# board.net
KiCad netlist of a schematic drawn in EAGLE
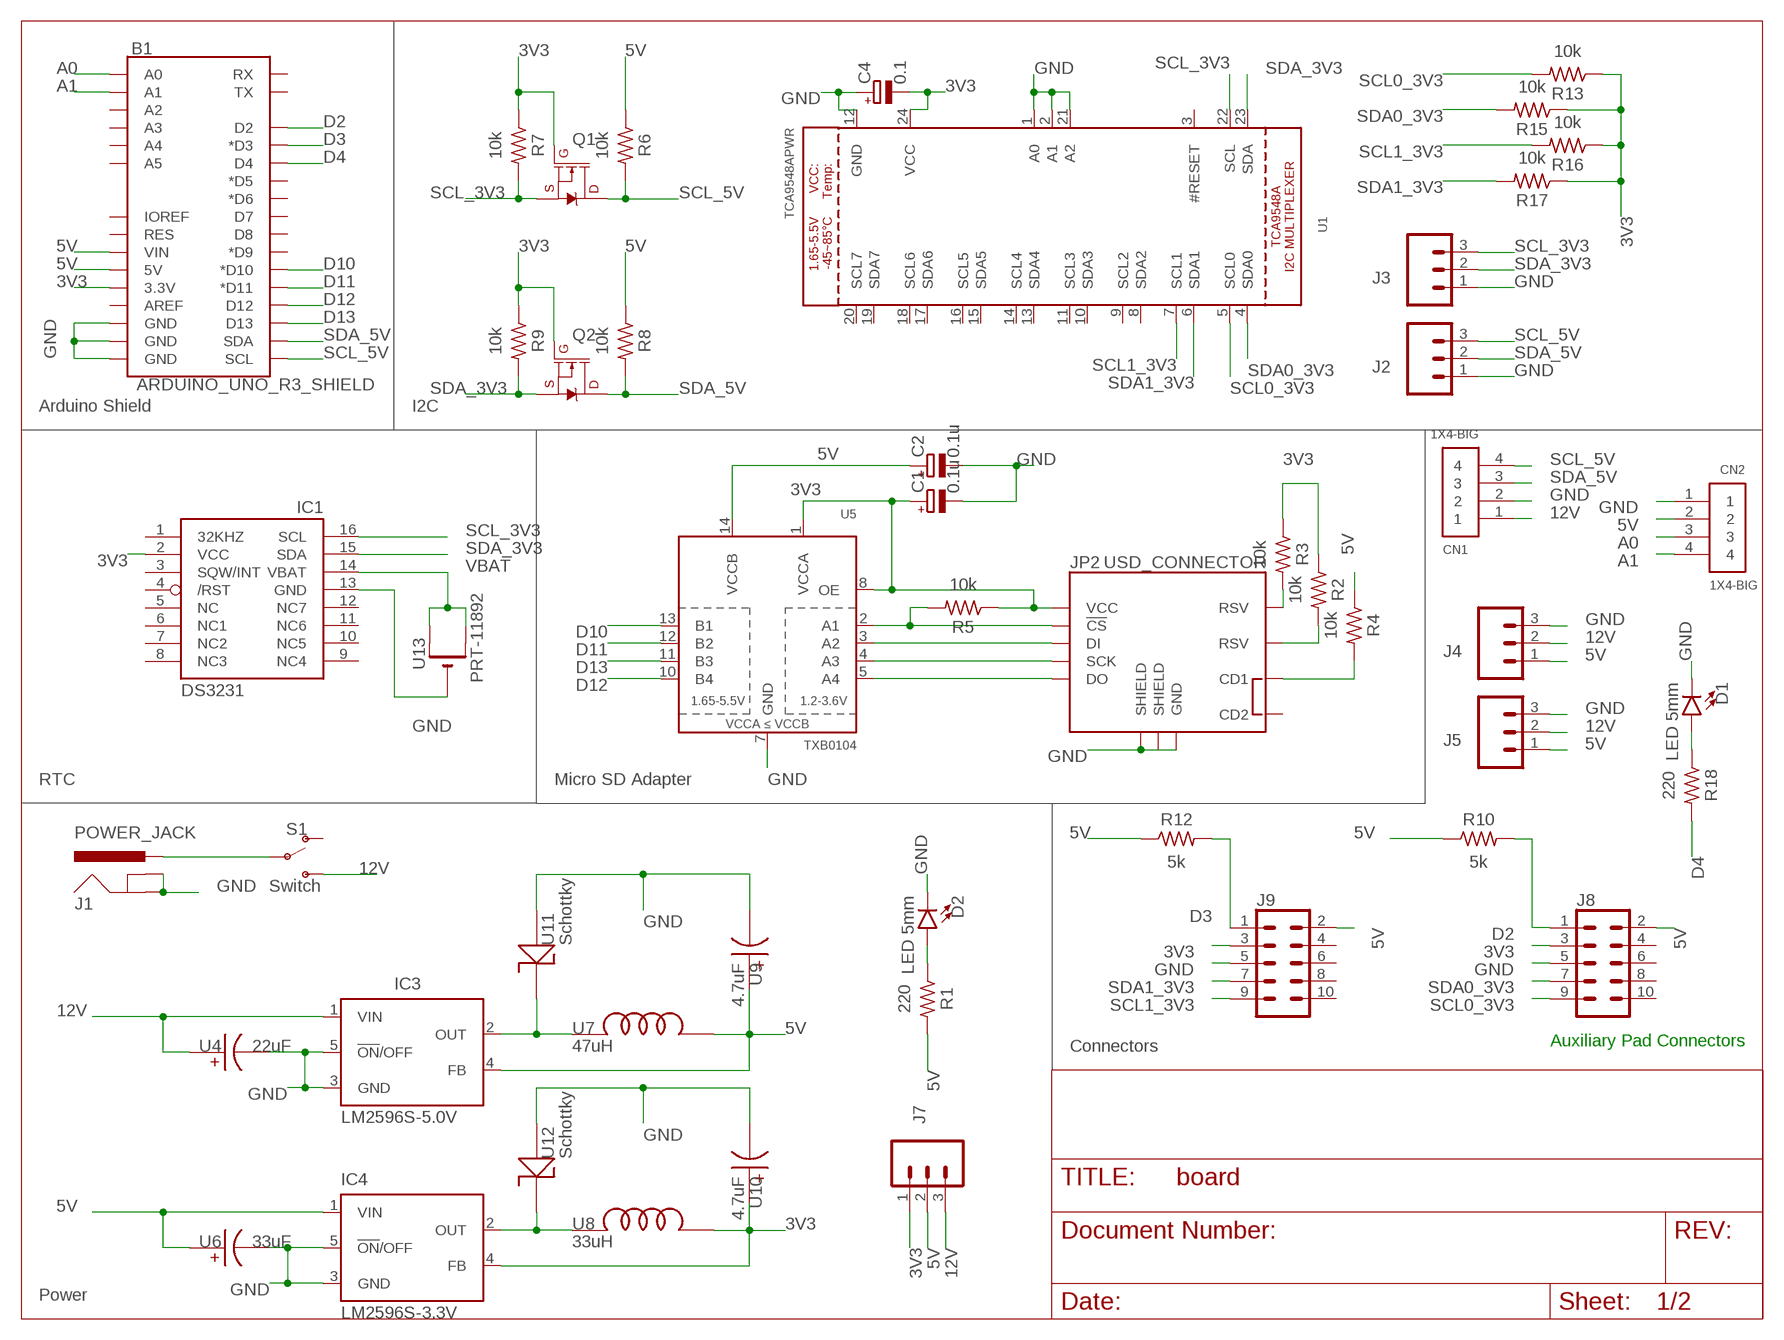
[diagram p0: schematic, sheet 1]
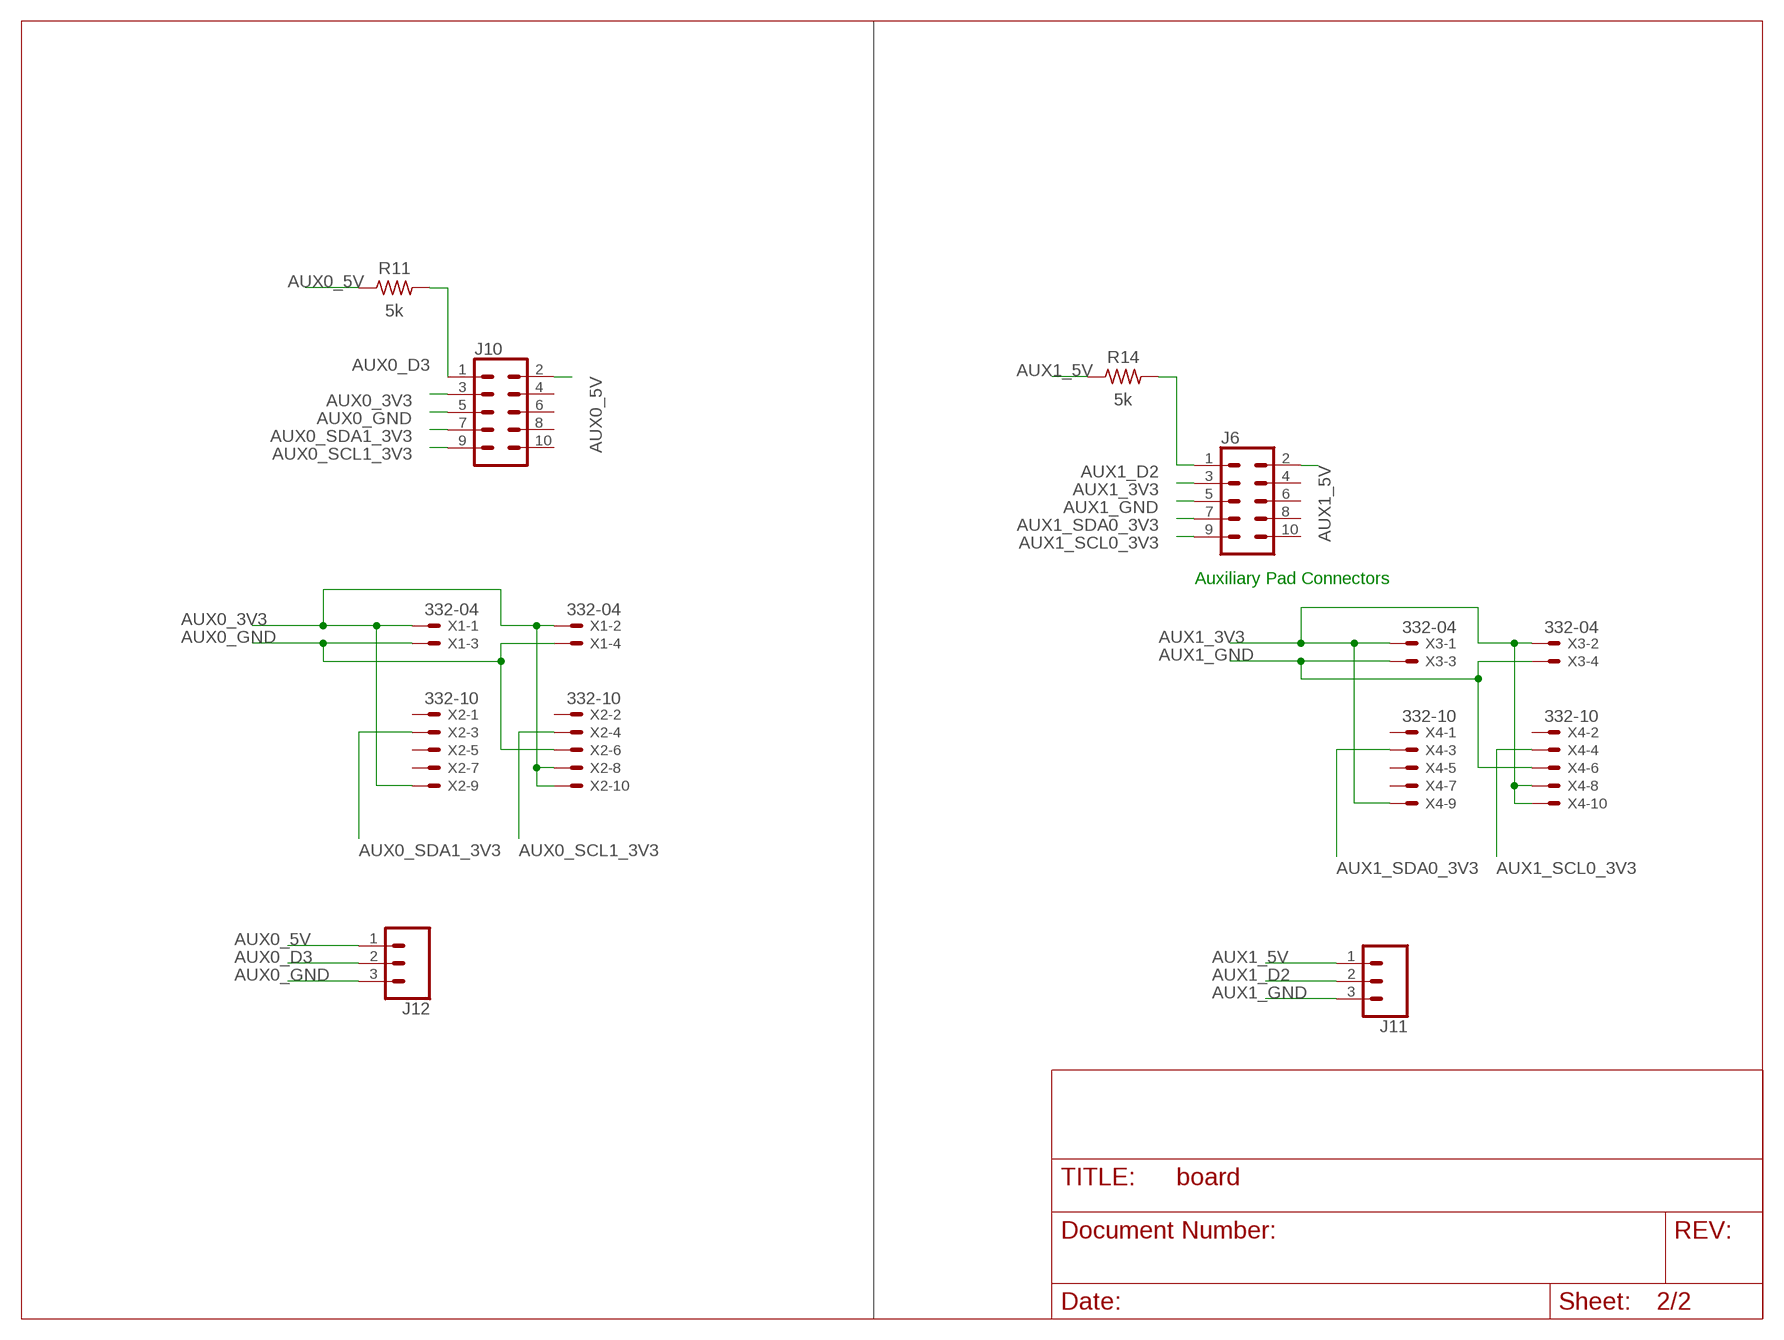
[diagram p1: schematic, sheet 2]

(export (version "E")
  (design (tool "Eeschema 10.0.6"))
  (components
    (comp (ref "B1")
      (value "ARDUINO_UNO_R3_SHIELD")
      (footprint "eagle-import:UNO_R3_SHIELD_NOLABELS_LOCK")
      (libsource (lib "eagle-import") (part "ARDUINO_UNO_R3_SHIELDUNO_R3_SHIELD_NOLABELS_LOCK"))
    )
    (comp (ref "C1")
      (value "0.1u")
      (footprint "eagle-import:CAPMP3216X180N")
      (libsource (lib "eagle-import") (part "C-POLTANTALUM-1206(3216-METRIC)_"))
    )
    (comp (ref "C2")
      (value "0.1u")
      (footprint "eagle-import:CAPMP3216X180N")
      (libsource (lib "eagle-import") (part "C-POLTANTALUM-1206(3216-METRIC)_"))
    )
    (comp (ref "C4")
      (value "0.1")
      (footprint "eagle-import:CAPMP3216X180N")
      (libsource (lib "eagle-import") (part "C-POLTANTALUM-1206(3216-METRIC)_"))
    )
    (comp (ref "CN1")
      (value "1X4-BIG")
      (footprint "eagle-import:1X04-BIG")
      (libsource (lib "eagle-import") (part "1X4-BIG"))
    )
    (comp (ref "CN2")
      (value "1X4-BIG")
      (footprint "eagle-import:1X04-BIG")
      (libsource (lib "eagle-import") (part "1X4-BIG"))
    )
    (comp (ref "D1")
      (value "LED 5mm")
      (footprint "eagle-import:LED_5MM")
      (fields (field (name "PARTNO") "FLC INVENTORY"))
      (libsource (lib "eagle-import") (part "LED5MM"))
    )
    (comp (ref "D2")
      (value "LED 5mm")
      (footprint "eagle-import:LED_5MM")
      (fields (field (name "PARTNO") "FLC INVENTORY"))
      (libsource (lib "eagle-import") (part "LED5MM"))
    )
    (comp (ref "IC1")
      (value "DS3231/SO")
      (footprint "eagle-import:SO16W")
      (libsource (lib "eagle-import") (part "DS3231/SO"))
    )
    (comp (ref "IC3")
      (value "LM2596S-5.0V")
      (footprint "eagle-import:TO263-5")
      (fields
        (field (name "MF") "NATIONAL SEMICONDUCTOR")
        (field (name "MPN") "LM2596S-ADJ/NOPB")
        (field (name "PARTNO") "FLC INVENTORY")
      )
      (libsource (lib "eagle-import") (part "LM2596S"))
    )
    (comp (ref "IC4")
      (value "LM2596S-3.3V")
      (footprint "eagle-import:TO263-5")
      (fields
        (field (name "MF") "NATIONAL SEMICONDUCTOR")
        (field (name "MPN") "LM2596S-ADJ/NOPB")
        (field (name "PARTNO") "FLC INVENTORY")
      )
      (libsource (lib "eagle-import") (part "LM2596S"))
    )
    (comp (ref "J1")
      (value "POWER_JACK")
      (footprint "eagle-import:POWER_JACK_PTH")
      (fields (field (name "PARTNO") "FLC INVENTORY"))
      (libsource (lib "eagle-import") (part "POWER_JACK"))
    )
    (comp (ref "J2")
      (value "3-Pin Screw Terminal 5mm")
      (footprint "eagle-import:SCREWTERMINAL-5MM-3")
      (fields (field (name "PARTNO") "2057-EB21A-03-C-ND"))
      (libsource (lib "eagle-import") (part "CONN_03-SCREW-5MM"))
    )
    (comp (ref "J3")
      (value "3-Pin Screw Terminal 5mm")
      (footprint "eagle-import:SCREWTERMINAL-5MM-3")
      (fields (field (name "PARTNO") "2057-EB21A-03-C-ND"))
      (libsource (lib "eagle-import") (part "CONN_03-SCREW-5MM"))
    )
    (comp (ref "J4")
      (value "3-Pin Screw Terminal 5mm")
      (footprint "eagle-import:SCREWTERMINAL-5MM-3")
      (fields (field (name "PARTNO") "2057-EB21A-03-C-ND"))
      (libsource (lib "eagle-import") (part "CONN_03-SCREW-5MM"))
    )
    (comp (ref "J5")
      (value "3-Pin Screw Terminal 5mm")
      (footprint "eagle-import:SCREWTERMINAL-5MM-3")
      (fields (field (name "PARTNO") "2057-EB21A-03-C-ND"))
      (libsource (lib "eagle-import") (part "CONN_03-SCREW-5MM"))
    )
    (comp (ref "J7")
      (value "3-Pin Screw Terminal 5mm")
      (footprint "eagle-import:SCREWTERMINAL-5MM-3")
      (fields (field (name "PARTNO") "2057-EB21A-03-C-ND"))
      (libsource (lib "eagle-import") (part "CONN_03-SCREW-5MM"))
    )
    (comp (ref "J8")
      (value "2x6 0.1\" Shrouded Female Header")
      (footprint "eagle-import:2X5-SHROUDED_LOCK")
      (fields (field (name "PARTNO") "PRT-08506 and PRT-10650"))
      (libsource (lib "eagle-import") (part "CONN_05X2SHD_LOCK"))
    )
    (comp (ref "J9")
      (value "2x6 0.1\" Shrouded Female Header")
      (footprint "eagle-import:2X5-SHROUDED_LOCK")
      (fields (field (name "PARTNO") "PRT-08506 and PRT-10650"))
      (libsource (lib "eagle-import") (part "CONN_05X2SHD_LOCK"))
    )
    (comp (ref "JP2")
      (value "USD_CONNECTOR")
      (footprint "eagle-import:MICRO-SD-SOCKET-PP")
      (libsource (lib "eagle-import") (part "USD_CONNECTOR"))
    )
    (comp (ref "Q1")
      (value "220mA/50V/3.5Ω")
      (footprint "eagle-import:SOT23-3")
      (libsource (lib "eagle-import") (part "MOSFET-NCH-BSS138"))
    )
    (comp (ref "Q2")
      (value "220mA/50V/3.5Ω")
      (footprint "eagle-import:SOT23-3")
      (libsource (lib "eagle-import") (part "MOSFET-NCH-BSS138"))
    )
    (comp (ref "R1")
      (value "220")
      (footprint "eagle-import:RESC1608X60")
      (libsource (lib "eagle-import") (part "R-USCHIP-0603(1608-METRIC)_"))
    )
    (comp (ref "R2")
      (value "10k")
      (footprint "eagle-import:RESC1608X60")
      (libsource (lib "eagle-import") (part "R-USCHIP-0603(1608-METRIC)_"))
    )
    (comp (ref "R3")
      (value "10k")
      (footprint "eagle-import:RESC1608X60")
      (libsource (lib "eagle-import") (part "R-USCHIP-0603(1608-METRIC)_"))
    )
    (comp (ref "R4")
      (value "10k")
      (footprint "eagle-import:RESC1608X60")
      (libsource (lib "eagle-import") (part "R-USCHIP-0603(1608-METRIC)_"))
    )
    (comp (ref "R5")
      (value "10k")
      (footprint "eagle-import:RESC1608X60")
      (libsource (lib "eagle-import") (part "R-USCHIP-0603(1608-METRIC)_"))
    )
    (comp (ref "R6")
      (value "10k")
      (footprint "eagle-import:RESC1608X60")
      (libsource (lib "eagle-import") (part "R-USCHIP-0603(1608-METRIC)_"))
    )
    (comp (ref "R7")
      (value "10k")
      (footprint "eagle-import:RESC1608X60")
      (libsource (lib "eagle-import") (part "R-USCHIP-0603(1608-METRIC)_"))
    )
    (comp (ref "R8")
      (value "10k")
      (footprint "eagle-import:RESC1608X60")
      (libsource (lib "eagle-import") (part "R-USCHIP-0603(1608-METRIC)_"))
    )
    (comp (ref "R9")
      (value "10k")
      (footprint "eagle-import:RESC1608X60")
      (libsource (lib "eagle-import") (part "R-USCHIP-0603(1608-METRIC)_"))
    )
    (comp (ref "R10")
      (value "5k")
      (footprint "eagle-import:RESC1608X60")
      (libsource (lib "eagle-import") (part "R-USCHIP-0603(1608-METRIC)_"))
    )
    (comp (ref "R12")
      (value "5k")
      (footprint "eagle-import:RESC1608X60")
      (libsource (lib "eagle-import") (part "R-USCHIP-0603(1608-METRIC)_"))
    )
    (comp (ref "R13")
      (value "10k")
      (footprint "eagle-import:RESC1608X60")
      (libsource (lib "eagle-import") (part "R-USCHIP-0603(1608-METRIC)_"))
    )
    (comp (ref "R15")
      (value "10k")
      (footprint "eagle-import:RESC1608X60")
      (libsource (lib "eagle-import") (part "R-USCHIP-0603(1608-METRIC)_"))
    )
    (comp (ref "R16")
      (value "10k")
      (footprint "eagle-import:RESC1608X60")
      (libsource (lib "eagle-import") (part "R-USCHIP-0603(1608-METRIC)_"))
    )
    (comp (ref "R17")
      (value "10k")
      (footprint "eagle-import:RESC1608X60")
      (libsource (lib "eagle-import") (part "R-USCHIP-0603(1608-METRIC)_"))
    )
    (comp (ref "R18")
      (value "220")
      (footprint "eagle-import:RESC1608X60")
      (libsource (lib "eagle-import") (part "R-USCHIP-0603(1608-METRIC)_"))
    )
    (comp (ref "S1")
      (value "Switch")
      (footprint "eagle-import:SWITCH_SPDT_PTH_11.6X4.0MM")
      (fields (field (name "PARTNO") "EG2355-ND"))
      (libsource (lib "eagle-import") (part "SWITCH-SPDT-PTH-11.6X4.0MM"))
    )
    (comp (ref "U1")
      (value "TCA9548APWR")
      (footprint "eagle-import:TSSOP24")
      (libsource (lib "eagle-import") (part "TCA9548A"))
    )
    (comp (ref "U4")
      (value "22uF")
      (footprint "eagle-import:CAP_ALUM_22UF_20%_63V_SMD")
      (fields (field (name "PARTNO") "FLC INVENTORY"))
      (libsource (lib "eagle-import") (part "CAP_ALUM_22UF_20%_63V_SMD"))
    )
    (comp (ref "U5")
      (value "TXB0104")
      (footprint "eagle-import:SO14")
      (libsource (lib "eagle-import") (part "TXB0104PWRSOIC14"))
    )
    (comp (ref "U6")
      (value "33uF")
      (footprint "eagle-import:CAP_ALUM_33UF_20%_63V_SMD")
      (fields (field (name "PARTNO") "FLC INVENTORY"))
      (libsource (lib "eagle-import") (part "CAP_ALUM_33UF_20%_63V_SMD"))
    )
    (comp (ref "U7")
      (value "47uH")
      (footprint "eagle-import:FIXED_IND_47UH_3.8A_60_MOHM_SMD")
      (fields (field (name "PARTNO") "FLC INVENTORY"))
      (libsource (lib "eagle-import") (part "FIXED_IND_47UH_3.8A_60_MOHM_SMD"))
    )
    (comp (ref "U8")
      (value "33uH")
      (footprint "eagle-import:FIXED_IND_47UH_3.8A_60_MOHM_SMD")
      (fields (field (name "PARTNO") "FLC INVENTORY"))
      (libsource (lib "eagle-import") (part "FIXED_IND_47UH_3.8A_60_MOHM_SMD"))
    )
    (comp (ref "U9")
      (value "4.7uF")
      (footprint "eagle-import:CAP_ALUM_4.7UF_20%_100V_SMD")
      (fields (field (name "PARTNO") "FLC INVENTORY"))
      (libsource (lib "eagle-import") (part "CAP_ALUM_4.7_UF_20%_100V_SMD"))
    )
    (comp (ref "U10")
      (value "4.7uF")
      (footprint "eagle-import:CAP_ALUM_4.7UF_20%_100V_SMD")
      (fields (field (name "PARTNO") "FLC INVENTORY"))
      (libsource (lib "eagle-import") (part "CAP_ALUM_4.7_UF_20%_100V_SMD"))
    )
    (comp (ref "U11")
      (value "Schottky")
      (footprint "eagle-import:DIODE_SCHOTTKY_40V_3A_SMC")
      (fields (field (name "PARTNO") "FLC INVENTORY"))
      (libsource (lib "eagle-import") (part "DIODE_SCHOTTKY_40V_3A_SMC"))
    )
    (comp (ref "U12")
      (value "Schottky")
      (footprint "eagle-import:DIODE_SCHOTTKY_40V_3A_SMC")
      (fields (field (name "PARTNO") "FLC INVENTORY"))
      (libsource (lib "eagle-import") (part "DIODE_SCHOTTKY_40V_3A_SMC"))
    )
    (comp (ref "U13")
      (value "PRT-11892")
      (footprint "eagle-import:CR2032-SMD")
      (libsource (lib "eagle-import") (part "CR2032SMT"))
    )
    (comp (ref "J6")
      (value "2x6 0.1\" Shrouded Female Header")
      (footprint "eagle-import:2X5-SHROUDED_LOCK")
      (fields (field (name "PARTNO") "PRT-08506 and PRT-10650"))
      (libsource (lib "eagle-import") (part "CONN_05X2SHD_LOCK"))
    )
    (comp (ref "J10")
      (value "2x6 0.1\" Shrouded Female Header")
      (footprint "eagle-import:2X5-SHROUDED_LOCK")
      (fields (field (name "PARTNO") "PRT-08506 and PRT-10650"))
      (libsource (lib "eagle-import") (part "CONN_05X2SHD_LOCK"))
    )
    (comp (ref "J11")
      (value "CONN_03")
      (footprint "eagle-import:1X03")
      (libsource (lib "eagle-import") (part "CONN_03"))
    )
    (comp (ref "J12")
      (value "CONN_03")
      (footprint "eagle-import:1X03")
      (libsource (lib "eagle-import") (part "CONN_03"))
    )
    (comp (ref "R11")
      (value "5k")
      (footprint "eagle-import:RESC1608X60")
      (libsource (lib "eagle-import") (part "R-USCHIP-0603(1608-METRIC)_"))
    )
    (comp (ref "R14")
      (value "5k")
      (footprint "eagle-import:RESC1608X60")
      (libsource (lib "eagle-import") (part "R-USCHIP-0603(1608-METRIC)_"))
    )
    (comp (ref "X1")
      (value "332-04")
      (footprint "eagle-import:332-04")
      (libsource (lib "eagle-import") (part "332-04"))
    )
    (comp (ref "X2")
      (value "332-10")
      (footprint "eagle-import:332-10")
      (libsource (lib "eagle-import") (part "332-10"))
    )
    (comp (ref "X3")
      (value "332-04")
      (footprint "eagle-import:332-04")
      (libsource (lib "eagle-import") (part "332-04"))
    )
    (comp (ref "X4")
      (value "332-10")
      (footprint "eagle-import:332-10")
      (libsource (lib "eagle-import") (part "332-10"))
    )
  )
  (nets
    (net (code "1") (name "3V3") (class "Default")
      (node (ref "B1") (pin "3.3V") (pinfunction "3.3V_3.3V") (pintype "bidirectional"))
      (node (ref "C1") (pin "1") (pinfunction "+_1") (pintype "passive"))
      (node (ref "C4") (pin "2") (pinfunction "-_2") (pintype "passive"))
      (node (ref "IC1") (pin "2") (pinfunction "VCC_2") (pintype "power_in"))
      (node (ref "IC4") (pin "4") (pinfunction "FB_4") (pintype "input"))
      (node (ref "J7") (pin "1") (pinfunction "1_1") (pintype "passive"))
      (node (ref "J8") (pin "3") (pinfunction "3_3") (pintype "passive"))
      (node (ref "J9") (pin "3") (pinfunction "3_3") (pintype "passive"))
      (node (ref "JP2") (pin "VCC") (pinfunction "VCC_VCC") (pintype "bidirectional"))
      (node (ref "Q1") (pin "1") (pinfunction "G_1") (pintype "bidirectional"))
      (node (ref "Q2") (pin "1") (pinfunction "G_1") (pintype "bidirectional"))
      (node (ref "R13") (pin "1") (pinfunction "1_1") (pintype "passive"))
      (node (ref "R15") (pin "1") (pinfunction "1_1") (pintype "passive"))
      (node (ref "R16") (pin "1") (pinfunction "1_1") (pintype "passive"))
      (node (ref "R17") (pin "1") (pinfunction "1_1") (pintype "passive"))
      (node (ref "R2") (pin "1") (pinfunction "1_1") (pintype "passive"))
      (node (ref "R3") (pin "1") (pinfunction "1_1") (pintype "passive"))
      (node (ref "R5") (pin "1") (pinfunction "1_1") (pintype "passive"))
      (node (ref "R7") (pin "1") (pinfunction "1_1") (pintype "passive"))
      (node (ref "R9") (pin "1") (pinfunction "1_1") (pintype "passive"))
      (node (ref "U1") (pin "24") (pinfunction "VCC_24") (pintype "bidirectional"))
      (node (ref "U10") (pin "P$2") (pinfunction "P$2_P$2") (pintype "bidirectional"))
      (node (ref "U5") (pin "1") (pinfunction "VCCA_1") (pintype "bidirectional"))
      (node (ref "U5") (pin "8") (pinfunction "OE_8") (pintype "bidirectional"))
      (node (ref "U8") (pin "P$2") (pinfunction "P$2_P$2") (pintype "bidirectional"))
    )
    (net (code "2") (name "5V") (class "Default")
      (node (ref "B1") (pin "5V") (pinfunction "5V_5V") (pintype "bidirectional"))
      (node (ref "B1") (pin "VIN") (pinfunction "VIN_VIN") (pintype "bidirectional"))
      (node (ref "C2") (pin "1") (pinfunction "+_1") (pintype "passive"))
      (node (ref "CN2") (pin "2") (pinfunction "2_2") (pintype "bidirectional"))
      (node (ref "IC3") (pin "4") (pinfunction "FB_4") (pintype "input"))
      (node (ref "IC4") (pin "1") (pinfunction "VIN_1") (pintype "input"))
      (node (ref "J4") (pin "1") (pinfunction "1_1") (pintype "passive"))
      (node (ref "J5") (pin "1") (pinfunction "1_1") (pintype "passive"))
      (node (ref "J7") (pin "2") (pinfunction "2_2") (pintype "passive"))
      (node (ref "J8") (pin "2") (pinfunction "2_2") (pintype "passive"))
      (node (ref "J9") (pin "2") (pinfunction "2_2") (pintype "passive"))
      (node (ref "R1") (pin "2") (pinfunction "2_2") (pintype "passive"))
      (node (ref "R10") (pin "1") (pinfunction "1_1") (pintype "passive"))
      (node (ref "R12") (pin "1") (pinfunction "1_1") (pintype "passive"))
      (node (ref "R4") (pin "1") (pinfunction "1_1") (pintype "passive"))
      (node (ref "R6") (pin "1") (pinfunction "1_1") (pintype "passive"))
      (node (ref "R8") (pin "1") (pinfunction "1_1") (pintype "passive"))
      (node (ref "U5") (pin "14") (pinfunction "VCCB_14") (pintype "bidirectional"))
      (node (ref "U6") (pin "P$2") (pinfunction "P$2_P$2") (pintype "bidirectional"))
      (node (ref "U7") (pin "P$2") (pinfunction "P$2_P$2") (pintype "bidirectional"))
      (node (ref "U9") (pin "P$2") (pinfunction "P$2_P$2") (pintype "bidirectional"))
    )
    (net (code "3") (name "12V") (class "Default")
      (node (ref "CN1") (pin "1") (pinfunction "1_1") (pintype "bidirectional"))
      (node (ref "IC3") (pin "1") (pinfunction "VIN_1") (pintype "input"))
      (node (ref "J4") (pin "2") (pinfunction "2_2") (pintype "passive"))
      (node (ref "J5") (pin "2") (pinfunction "2_2") (pintype "passive"))
      (node (ref "J7") (pin "3") (pinfunction "3_3") (pintype "passive"))
      (node (ref "S1") (pin "3") (pinfunction "S_3") (pintype "passive"))
      (node (ref "U4") (pin "P$2") (pinfunction "P$2_P$2") (pintype "bidirectional"))
    )
    (net (code "4") (name "A0") (class "Default")
      (node (ref "B1") (pin "A0") (pinfunction "A0_A0") (pintype "bidirectional"))
      (node (ref "CN2") (pin "3") (pinfunction "3_3") (pintype "bidirectional"))
    )
    (net (code "5") (name "A1") (class "Default")
      (node (ref "B1") (pin "A1") (pinfunction "A1_A1") (pintype "bidirectional"))
      (node (ref "CN2") (pin "4") (pinfunction "4_4") (pintype "bidirectional"))
    )
    (net (code "6") (name "AUX0_3V3") (class "Default")
      (node (ref "J10") (pin "3") (pinfunction "3_3") (pintype "passive"))
      (node (ref "X1") (pin "1") (pinfunction "S_1") (pintype "passive"))
      (node (ref "X1") (pin "2") (pinfunction "S_2") (pintype "passive"))
      (node (ref "X2") (pin "10") (pinfunction "S_10") (pintype "passive"))
      (node (ref "X2") (pin "8") (pinfunction "S_8") (pintype "passive"))
      (node (ref "X2") (pin "9") (pinfunction "S_9") (pintype "passive"))
    )
    (net (code "7") (name "AUX0_5V") (class "Default")
      (node (ref "J10") (pin "2") (pinfunction "2_2") (pintype "passive"))
      (node (ref "J12") (pin "1") (pinfunction "1_1") (pintype "passive"))
      (node (ref "R11") (pin "1") (pinfunction "1_1") (pintype "passive"))
    )
    (net (code "8") (name "AUX0_D3") (class "Default")
      (node (ref "J10") (pin "1") (pinfunction "1_1") (pintype "passive"))
      (node (ref "J12") (pin "2") (pinfunction "2_2") (pintype "passive"))
      (node (ref "R11") (pin "2") (pinfunction "2_2") (pintype "passive"))
    )
    (net (code "9") (name "AUX0_GND") (class "Default")
      (node (ref "J10") (pin "5") (pinfunction "5_5") (pintype "passive"))
      (node (ref "J12") (pin "3") (pinfunction "3_3") (pintype "passive"))
      (node (ref "X1") (pin "3") (pinfunction "S_3") (pintype "passive"))
      (node (ref "X1") (pin "4") (pinfunction "S_4") (pintype "passive"))
      (node (ref "X2") (pin "6") (pinfunction "S_6") (pintype "passive"))
    )
    (net (code "10") (name "AUX0_SCL1_3V3") (class "Default")
      (node (ref "J10") (pin "9") (pinfunction "9_9") (pintype "passive"))
      (node (ref "X2") (pin "4") (pinfunction "S_4") (pintype "passive"))
    )
    (net (code "11") (name "AUX0_SDA1_3V3") (class "Default")
      (node (ref "J10") (pin "7") (pinfunction "7_7") (pintype "passive"))
      (node (ref "X2") (pin "3") (pinfunction "S_3") (pintype "passive"))
    )
    (net (code "12") (name "AUX1_3V3") (class "Default")
      (node (ref "J6") (pin "3") (pinfunction "3_3") (pintype "passive"))
      (node (ref "X3") (pin "1") (pinfunction "S_1") (pintype "passive"))
      (node (ref "X3") (pin "2") (pinfunction "S_2") (pintype "passive"))
      (node (ref "X4") (pin "10") (pinfunction "S_10") (pintype "passive"))
      (node (ref "X4") (pin "8") (pinfunction "S_8") (pintype "passive"))
      (node (ref "X4") (pin "9") (pinfunction "S_9") (pintype "passive"))
    )
    (net (code "13") (name "AUX1_5V") (class "Default")
      (node (ref "J11") (pin "1") (pinfunction "1_1") (pintype "passive"))
      (node (ref "J6") (pin "2") (pinfunction "2_2") (pintype "passive"))
      (node (ref "R14") (pin "1") (pinfunction "1_1") (pintype "passive"))
    )
    (net (code "14") (name "AUX1_D2") (class "Default")
      (node (ref "J11") (pin "2") (pinfunction "2_2") (pintype "passive"))
      (node (ref "J6") (pin "1") (pinfunction "1_1") (pintype "passive"))
      (node (ref "R14") (pin "2") (pinfunction "2_2") (pintype "passive"))
    )
    (net (code "15") (name "AUX1_GND") (class "Default")
      (node (ref "J11") (pin "3") (pinfunction "3_3") (pintype "passive"))
      (node (ref "J6") (pin "5") (pinfunction "5_5") (pintype "passive"))
      (node (ref "X3") (pin "3") (pinfunction "S_3") (pintype "passive"))
      (node (ref "X3") (pin "4") (pinfunction "S_4") (pintype "passive"))
      (node (ref "X4") (pin "6") (pinfunction "S_6") (pintype "passive"))
    )
    (net (code "16") (name "AUX1_SCL0_3V3") (class "Default")
      (node (ref "J6") (pin "9") (pinfunction "9_9") (pintype "passive"))
      (node (ref "X4") (pin "4") (pinfunction "S_4") (pintype "passive"))
    )
    (net (code "17") (name "AUX1_SDA0_3V3") (class "Default")
      (node (ref "J6") (pin "7") (pinfunction "7_7") (pintype "passive"))
      (node (ref "X4") (pin "3") (pinfunction "S_3") (pintype "passive"))
    )
    (net (code "18") (name "D2") (class "Default")
      (node (ref "B1") (pin "D2") (pinfunction "D2_D2") (pintype "bidirectional"))
      (node (ref "J8") (pin "1") (pinfunction "1_1") (pintype "passive"))
      (node (ref "R10") (pin "2") (pinfunction "2_2") (pintype "passive"))
    )
    (net (code "19") (name "D3") (class "Default")
      (node (ref "B1") (pin "D3") (pinfunction "*D3_D3") (pintype "bidirectional"))
      (node (ref "J9") (pin "1") (pinfunction "1_1") (pintype "passive"))
      (node (ref "R12") (pin "2") (pinfunction "2_2") (pintype "passive"))
    )
    (net (code "20") (name "D4") (class "Default")
      (node (ref "B1") (pin "D4") (pinfunction "D4_D4") (pintype "bidirectional"))
      (node (ref "R18") (pin "2") (pinfunction "2_2") (pintype "passive"))
    )
    (net (code "21") (name "D10") (class "Default")
      (node (ref "B1") (pin "D10") (pinfunction "*D10_D10") (pintype "bidirectional"))
      (node (ref "U5") (pin "13") (pinfunction "B1_13") (pintype "bidirectional"))
    )
    (net (code "22") (name "D11") (class "Default")
      (node (ref "B1") (pin "D11") (pinfunction "*D11_D11") (pintype "bidirectional"))
      (node (ref "U5") (pin "12") (pinfunction "B2_12") (pintype "bidirectional"))
    )
    (net (code "23") (name "D12") (class "Default")
      (node (ref "B1") (pin "D12") (pinfunction "D12_D12") (pintype "bidirectional"))
      (node (ref "U5") (pin "10") (pinfunction "B4_10") (pintype "bidirectional"))
    )
    (net (code "24") (name "D13") (class "Default")
      (node (ref "B1") (pin "D13") (pinfunction "D13_D13") (pintype "bidirectional"))
      (node (ref "U5") (pin "11") (pinfunction "B3_11") (pintype "bidirectional"))
    )
    (net (code "25") (name "GND") (class "Default")
      (node (ref "B1") (pin "GND@0") (pinfunction "GND_GND@0") (pintype "bidirectional"))
      (node (ref "B1") (pin "GND@1") (pinfunction "GND_GND@1") (pintype "bidirectional"))
      (node (ref "B1") (pin "GND@2") (pinfunction "GND_GND@2") (pintype "bidirectional"))
      (node (ref "C1") (pin "2") (pinfunction "-_2") (pintype "passive"))
      (node (ref "C2") (pin "2") (pinfunction "-_2") (pintype "passive"))
      (node (ref "C4") (pin "1") (pinfunction "+_1") (pintype "passive"))
      (node (ref "CN1") (pin "2") (pinfunction "2_2") (pintype "bidirectional"))
      (node (ref "CN2") (pin "1") (pinfunction "1_1") (pintype "bidirectional"))
      (node (ref "D1") (pin "K") (pinfunction "C_K") (pintype "passive"))
      (node (ref "D2") (pin "K") (pinfunction "C_K") (pintype "passive"))
      (node (ref "IC1") (pin "13") (pinfunction "GND_13") (pintype "power_in"))
      (node (ref "IC3") (pin "3") (pinfunction "GND_3") (pintype "power_in"))
      (node (ref "IC3") (pin "5") (pinfunction "~{ON}/OFF_5") (pintype "input"))
      (node (ref "IC4") (pin "3") (pinfunction "GND_3") (pintype "power_in"))
      (node (ref "IC4") (pin "5") (pinfunction "~{ON}/OFF_5") (pintype "input"))
      (node (ref "J1") (pin "GND") (pinfunction "GND_GND") (pintype "bidirectional"))
      (node (ref "J1") (pin "GNDBREAK") (pinfunction "GNDBREAK_GNDBREAK") (pintype "bidirectional"))
      (node (ref "J2") (pin "1") (pinfunction "1_1") (pintype "passive"))
      (node (ref "J3") (pin "1") (pinfunction "1_1") (pintype "passive"))
      (node (ref "J4") (pin "3") (pinfunction "3_3") (pintype "passive"))
      (node (ref "J5") (pin "3") (pinfunction "3_3") (pintype "passive"))
      (node (ref "J8") (pin "5") (pinfunction "5_5") (pintype "passive"))
      (node (ref "J9") (pin "5") (pinfunction "5_5") (pintype "passive"))
      (node (ref "JP2") (pin "GND") (pinfunction "GND_GND") (pintype "bidirectional"))
      (node (ref "JP2") (pin "GND1") (pinfunction "SHIELD_GND1") (pintype "bidirectional"))
      (node (ref "JP2") (pin "GND3") (pinfunction "SHIELD_GND3") (pintype "bidirectional"))
      (node (ref "U1") (pin "1") (pinfunction "A0_1") (pintype "bidirectional"))
      (node (ref "U1") (pin "12") (pinfunction "GND_12") (pintype "bidirectional"))
      (node (ref "U1") (pin "2") (pinfunction "A1_2") (pintype "bidirectional"))
      (node (ref "U1") (pin "21") (pinfunction "A2_21") (pintype "bidirectional"))
      (node (ref "U10") (pin "P$1") (pinfunction "P$1_P$1") (pintype "bidirectional"))
      (node (ref "U11") (pin "P$1") (pinfunction "P$1_P$1") (pintype "bidirectional"))
      (node (ref "U12") (pin "P$1") (pinfunction "P$1_P$1") (pintype "bidirectional"))
      (node (ref "U13") (pin "-") (pinfunction "-_-") (pintype "passive"))
      (node (ref "U4") (pin "P$1") (pinfunction "P$1_P$1") (pintype "bidirectional"))
      (node (ref "U5") (pin "7") (pinfunction "GND_7") (pintype "bidirectional"))
      (node (ref "U6") (pin "P$1") (pinfunction "P$1_P$1") (pintype "bidirectional"))
      (node (ref "U9") (pin "P$1") (pinfunction "P$1_P$1") (pintype "bidirectional"))
    )
    (net (code "26") (name "Net-(D1-PadA)") (class "Default")
      (node (ref "D1") (pin "A") (pinfunction "A_A") (pintype "passive"))
      (node (ref "R18") (pin "1") (pinfunction "1_1") (pintype "passive"))
    )
    (net (code "27") (name "Net-(D2-PadA)") (class "Default")
      (node (ref "D2") (pin "A") (pinfunction "A_A") (pintype "passive"))
      (node (ref "R1") (pin "1") (pinfunction "1_1") (pintype "passive"))
    )
    (net (code "28") (name "Net-(IC3-OUT)") (class "Default")
      (node (ref "IC3") (pin "2") (pinfunction "OUT_2") (pintype "output"))
      (node (ref "U11") (pin "P$2") (pinfunction "P$2_P$2") (pintype "bidirectional"))
      (node (ref "U7") (pin "P$1") (pinfunction "P$1_P$1") (pintype "bidirectional"))
    )
    (net (code "29") (name "Net-(IC4-OUT)") (class "Default")
      (node (ref "IC4") (pin "2") (pinfunction "OUT_2") (pintype "output"))
      (node (ref "U12") (pin "P$2") (pinfunction "P$2_P$2") (pintype "bidirectional"))
      (node (ref "U8") (pin "P$1") (pinfunction "P$1_P$1") (pintype "bidirectional"))
    )
    (net (code "30") (name "Net-(JP2-PadCD1)") (class "Default")
      (node (ref "JP2") (pin "CD1") (pinfunction "CD1_CD1") (pintype "bidirectional"))
      (node (ref "R4") (pin "2") (pinfunction "2_2") (pintype "passive"))
    )
    (net (code "31") (name "Net-(JP2-RSV-PadRSV1)") (class "Default")
      (node (ref "JP2") (pin "RSV1") (pinfunction "RSV_RSV1") (pintype "bidirectional"))
      (node (ref "R3") (pin "2") (pinfunction "2_2") (pintype "passive"))
    )
    (net (code "32") (name "Net-(JP2-RSV-PadRSV2)") (class "Default")
      (node (ref "JP2") (pin "RSV2") (pinfunction "RSV_RSV2") (pintype "bidirectional"))
      (node (ref "R2") (pin "2") (pinfunction "2_2") (pintype "passive"))
    )
    (net (code "33") (name "Net-(JP2-SCK)") (class "Default")
      (node (ref "JP2") (pin "SCLK") (pinfunction "SCK_SCLK") (pintype "bidirectional"))
      (node (ref "U5") (pin "4") (pinfunction "A3_4") (pintype "bidirectional"))
    )
    (net (code "34") (name "Net-(JP2-~{CS})") (class "Default")
      (node (ref "JP2") (pin "CS") (pinfunction "~{CS}_CS") (pintype "bidirectional"))
      (node (ref "R5") (pin "2") (pinfunction "2_2") (pintype "passive"))
      (node (ref "U5") (pin "2") (pinfunction "A1_2") (pintype "bidirectional"))
    )
    (net (code "35") (name "Net-(S1-P)") (class "Default")
      (node (ref "J1") (pin "PWR") (pinfunction "PWR_PWR") (pintype "bidirectional"))
      (node (ref "S1") (pin "2") (pinfunction "P_2") (pintype "passive"))
    )
    (net (code "36") (name "Net-(U5-A2)") (class "Default")
      (node (ref "JP2") (pin "DI") (pinfunction "DI_DI") (pintype "bidirectional"))
      (node (ref "U5") (pin "3") (pinfunction "A2_3") (pintype "bidirectional"))
    )
    (net (code "37") (name "Net-(U5-A4)") (class "Default")
      (node (ref "JP2") (pin "DO") (pinfunction "DO_DO") (pintype "bidirectional"))
      (node (ref "U5") (pin "5") (pinfunction "A4_5") (pintype "bidirectional"))
    )
    (net (code "38") (name "SCL0_3V3") (class "Default")
      (node (ref "J8") (pin "9") (pinfunction "9_9") (pintype "passive"))
      (node (ref "R13") (pin "2") (pinfunction "2_2") (pintype "passive"))
      (node (ref "U1") (pin "5") (pinfunction "SCL0_5") (pintype "bidirectional"))
    )
    (net (code "39") (name "SCL1_3V3") (class "Default")
      (node (ref "J9") (pin "9") (pinfunction "9_9") (pintype "passive"))
      (node (ref "R16") (pin "2") (pinfunction "2_2") (pintype "passive"))
      (node (ref "U1") (pin "7") (pinfunction "SCL1_7") (pintype "bidirectional"))
    )
    (net (code "40") (name "SCL_3V3") (class "Default")
      (node (ref "IC1") (pin "16") (pinfunction "SCL_16") (pintype "bidirectional"))
      (node (ref "J3") (pin "3") (pinfunction "3_3") (pintype "passive"))
      (node (ref "Q1") (pin "2") (pinfunction "S_2") (pintype "bidirectional"))
      (node (ref "R7") (pin "2") (pinfunction "2_2") (pintype "passive"))
      (node (ref "U1") (pin "22") (pinfunction "SCL_22") (pintype "bidirectional"))
    )
    (net (code "41") (name "SCL_5V") (class "Default")
      (node (ref "B1") (pin "SCL") (pinfunction "SCL_SCL") (pintype "bidirectional"))
      (node (ref "CN1") (pin "4") (pinfunction "4_4") (pintype "bidirectional"))
      (node (ref "J2") (pin "3") (pinfunction "3_3") (pintype "passive"))
      (node (ref "Q1") (pin "3") (pinfunction "D_3") (pintype "bidirectional"))
      (node (ref "R6") (pin "2") (pinfunction "2_2") (pintype "passive"))
    )
    (net (code "42") (name "SDA0_3V3") (class "Default")
      (node (ref "J8") (pin "7") (pinfunction "7_7") (pintype "passive"))
      (node (ref "R15") (pin "2") (pinfunction "2_2") (pintype "passive"))
      (node (ref "U1") (pin "4") (pinfunction "SDA0_4") (pintype "bidirectional"))
    )
    (net (code "43") (name "SDA1_3V3") (class "Default")
      (node (ref "J9") (pin "7") (pinfunction "7_7") (pintype "passive"))
      (node (ref "R17") (pin "2") (pinfunction "2_2") (pintype "passive"))
      (node (ref "U1") (pin "6") (pinfunction "SDA1_6") (pintype "bidirectional"))
    )
    (net (code "44") (name "SDA_3V3") (class "Default")
      (node (ref "IC1") (pin "15") (pinfunction "SDA_15") (pintype "bidirectional"))
      (node (ref "J3") (pin "2") (pinfunction "2_2") (pintype "passive"))
      (node (ref "Q2") (pin "2") (pinfunction "S_2") (pintype "bidirectional"))
      (node (ref "R9") (pin "2") (pinfunction "2_2") (pintype "passive"))
      (node (ref "U1") (pin "23") (pinfunction "SDA_23") (pintype "bidirectional"))
    )
    (net (code "45") (name "SDA_5V") (class "Default")
      (node (ref "B1") (pin "SDA") (pinfunction "SDA_SDA") (pintype "bidirectional"))
      (node (ref "CN1") (pin "3") (pinfunction "3_3") (pintype "bidirectional"))
      (node (ref "J2") (pin "2") (pinfunction "2_2") (pintype "passive"))
      (node (ref "Q2") (pin "3") (pinfunction "D_3") (pintype "bidirectional"))
      (node (ref "R8") (pin "2") (pinfunction "2_2") (pintype "passive"))
    )
    (net (code "46") (name "VBAT") (class "Default")
      (node (ref "IC1") (pin "14") (pinfunction "VBAT_14") (pintype "power_in"))
      (node (ref "U13") (pin "+$1") (pinfunction "+_+$1") (pintype "passive"))
      (node (ref "U13") (pin "+$2") (pinfunction "+1_+$2") (pintype "passive"))
    )
    (net (code "47") (name "unconnected-(B1-*D5-PadD5)") (class "Default")
      (node (ref "B1") (pin "D5") (pinfunction "*D5_D5") (pintype "bidirectional"))
    )
    (net (code "48") (name "unconnected-(B1-*D6-PadD6)") (class "Default")
      (node (ref "B1") (pin "D6") (pinfunction "*D6_D6") (pintype "bidirectional"))
    )
    (net (code "49") (name "unconnected-(B1-*D9-PadD9)") (class "Default")
      (node (ref "B1") (pin "D9") (pinfunction "*D9_D9") (pintype "bidirectional"))
    )
    (net (code "50") (name "unconnected-(B1-PadA2)") (class "Default")
      (node (ref "B1") (pin "A2") (pinfunction "A2_A2") (pintype "bidirectional"))
    )
    (net (code "51") (name "unconnected-(B1-PadA3)") (class "Default")
      (node (ref "B1") (pin "A3") (pinfunction "A3_A3") (pintype "bidirectional"))
    )
    (net (code "52") (name "unconnected-(B1-PadA4)") (class "Default")
      (node (ref "B1") (pin "A4") (pinfunction "A4_A4") (pintype "bidirectional"))
    )
    (net (code "53") (name "unconnected-(B1-PadA5)") (class "Default")
      (node (ref "B1") (pin "A5") (pinfunction "A5_A5") (pintype "bidirectional"))
    )
    (net (code "54") (name "unconnected-(B1-PadAREF)") (class "Default")
      (node (ref "B1") (pin "AREF") (pinfunction "AREF_AREF") (pintype "bidirectional"))
    )
    (net (code "55") (name "unconnected-(B1-PadD7)") (class "Default")
      (node (ref "B1") (pin "D7") (pinfunction "D7_D7") (pintype "bidirectional"))
    )
    (net (code "56") (name "unconnected-(B1-PadD8)") (class "Default")
      (node (ref "B1") (pin "D8") (pinfunction "D8_D8") (pintype "bidirectional"))
    )
    (net (code "57") (name "unconnected-(B1-PadIOREF)") (class "Default")
      (node (ref "B1") (pin "IOREF") (pinfunction "IOREF_IOREF") (pintype "bidirectional"))
    )
    (net (code "58") (name "unconnected-(B1-PadRES)") (class "Default")
      (node (ref "B1") (pin "RES") (pinfunction "RES_RES") (pintype "bidirectional"))
    )
    (net (code "59") (name "unconnected-(B1-PadRX)") (class "Default")
      (node (ref "B1") (pin "RX") (pinfunction "RX_RX") (pintype "bidirectional"))
    )
    (net (code "60") (name "unconnected-(B1-PadTX)") (class "Default")
      (node (ref "B1") (pin "TX") (pinfunction "TX_TX") (pintype "bidirectional"))
    )
    (net (code "61") (name "unconnected-(IC1-32KHZ-Pad1)") (class "Default")
      (node (ref "IC1") (pin "1") (pinfunction "32KHZ_1") (pintype "output"))
    )
    (net (code "62") (name "unconnected-(IC1-NC-Pad5)") (class "Default")
      (node (ref "IC1") (pin "5") (pinfunction "NC_5") (pintype "no_connect"))
    )
    (net (code "63") (name "unconnected-(IC1-NC1-Pad6)") (class "Default")
      (node (ref "IC1") (pin "6") (pinfunction "NC1_6") (pintype "no_connect"))
    )
    (net (code "64") (name "unconnected-(IC1-NC2-Pad7)") (class "Default")
      (node (ref "IC1") (pin "7") (pinfunction "NC2_7") (pintype "no_connect"))
    )
    (net (code "65") (name "unconnected-(IC1-NC3-Pad8)") (class "Default")
      (node (ref "IC1") (pin "8") (pinfunction "NC3_8") (pintype "no_connect"))
    )
    (net (code "66") (name "unconnected-(IC1-NC4-Pad9)") (class "Default")
      (node (ref "IC1") (pin "9") (pinfunction "NC4_9") (pintype "no_connect"))
    )
    (net (code "67") (name "unconnected-(IC1-NC5-Pad10)") (class "Default")
      (node (ref "IC1") (pin "10") (pinfunction "NC5_10") (pintype "no_connect"))
    )
    (net (code "68") (name "unconnected-(IC1-NC6-Pad11)") (class "Default")
      (node (ref "IC1") (pin "11") (pinfunction "NC6_11") (pintype "no_connect"))
    )
    (net (code "69") (name "unconnected-(IC1-NC7-Pad12)") (class "Default")
      (node (ref "IC1") (pin "12") (pinfunction "NC7_12") (pintype "no_connect"))
    )
    (net (code "70") (name "unconnected-(IC1-SQW{slash}INT-Pad3)") (class "Default")
      (node (ref "IC1") (pin "3") (pinfunction "SQW/INT_3") (pintype "output"))
    )
    (net (code "71") (name "unconnected-(IC1-{slash}RST-Pad4)") (class "Default")
      (node (ref "IC1") (pin "4") (pinfunction "/RST_4") (pintype "passive"))
    )
    (net (code "72") (name "unconnected-(J6-Pad4)") (class "Default")
      (node (ref "J6") (pin "4") (pinfunction "4_4") (pintype "passive"))
    )
    (net (code "73") (name "unconnected-(J6-Pad6)") (class "Default")
      (node (ref "J6") (pin "6") (pinfunction "6_6") (pintype "passive"))
    )
    (net (code "74") (name "unconnected-(J6-Pad8)") (class "Default")
      (node (ref "J6") (pin "8") (pinfunction "8_8") (pintype "passive"))
    )
    (net (code "75") (name "unconnected-(J6-Pad10)") (class "Default")
      (node (ref "J6") (pin "10") (pinfunction "10_10") (pintype "passive"))
    )
    (net (code "76") (name "unconnected-(J8-Pad4)") (class "Default")
      (node (ref "J8") (pin "4") (pinfunction "4_4") (pintype "passive"))
    )
    (net (code "77") (name "unconnected-(J8-Pad6)") (class "Default")
      (node (ref "J8") (pin "6") (pinfunction "6_6") (pintype "passive"))
    )
    (net (code "78") (name "unconnected-(J8-Pad8)") (class "Default")
      (node (ref "J8") (pin "8") (pinfunction "8_8") (pintype "passive"))
    )
    (net (code "79") (name "unconnected-(J8-Pad10)") (class "Default")
      (node (ref "J8") (pin "10") (pinfunction "10_10") (pintype "passive"))
    )
    (net (code "80") (name "unconnected-(J9-Pad4)") (class "Default")
      (node (ref "J9") (pin "4") (pinfunction "4_4") (pintype "passive"))
    )
    (net (code "81") (name "unconnected-(J9-Pad6)") (class "Default")
      (node (ref "J9") (pin "6") (pinfunction "6_6") (pintype "passive"))
    )
    (net (code "82") (name "unconnected-(J9-Pad8)") (class "Default")
      (node (ref "J9") (pin "8") (pinfunction "8_8") (pintype "passive"))
    )
    (net (code "83") (name "unconnected-(J9-Pad10)") (class "Default")
      (node (ref "J9") (pin "10") (pinfunction "10_10") (pintype "passive"))
    )
    (net (code "84") (name "unconnected-(J10-Pad4)") (class "Default")
      (node (ref "J10") (pin "4") (pinfunction "4_4") (pintype "passive"))
    )
    (net (code "85") (name "unconnected-(J10-Pad6)") (class "Default")
      (node (ref "J10") (pin "6") (pinfunction "6_6") (pintype "passive"))
    )
    (net (code "86") (name "unconnected-(J10-Pad8)") (class "Default")
      (node (ref "J10") (pin "8") (pinfunction "8_8") (pintype "passive"))
    )
    (net (code "87") (name "unconnected-(J10-Pad10)") (class "Default")
      (node (ref "J10") (pin "10") (pinfunction "10_10") (pintype "passive"))
    )
    (net (code "88") (name "unconnected-(JP2-PadCD2)") (class "Default")
      (node (ref "JP2") (pin "CD2") (pinfunction "CD2_CD2") (pintype "bidirectional"))
    )
    (net (code "89") (name "unconnected-(S1-O-Pad1)") (class "Default")
      (node (ref "S1") (pin "1") (pinfunction "O_1") (pintype "passive"))
    )
    (net (code "90") (name "unconnected-(U1-#RESET-Pad3)") (class "Default")
      (node (ref "U1") (pin "3") (pinfunction "#RESET_3") (pintype "bidirectional"))
    )
    (net (code "91") (name "unconnected-(U1-SCL2-Pad9)") (class "Default")
      (node (ref "U1") (pin "9") (pinfunction "SCL2_9") (pintype "bidirectional"))
    )
    (net (code "92") (name "unconnected-(U1-SCL3-Pad11)") (class "Default")
      (node (ref "U1") (pin "11") (pinfunction "SCL3_11") (pintype "bidirectional"))
    )
    (net (code "93") (name "unconnected-(U1-SCL4-Pad14)") (class "Default")
      (node (ref "U1") (pin "14") (pinfunction "SCL4_14") (pintype "bidirectional"))
    )
    (net (code "94") (name "unconnected-(U1-SCL5-Pad16)") (class "Default")
      (node (ref "U1") (pin "16") (pinfunction "SCL5_16") (pintype "bidirectional"))
    )
    (net (code "95") (name "unconnected-(U1-SCL6-Pad18)") (class "Default")
      (node (ref "U1") (pin "18") (pinfunction "SCL6_18") (pintype "bidirectional"))
    )
    (net (code "96") (name "unconnected-(U1-SCL7-Pad20)") (class "Default")
      (node (ref "U1") (pin "20") (pinfunction "SCL7_20") (pintype "bidirectional"))
    )
    (net (code "97") (name "unconnected-(U1-SDA2-Pad8)") (class "Default")
      (node (ref "U1") (pin "8") (pinfunction "SDA2_8") (pintype "bidirectional"))
    )
    (net (code "98") (name "unconnected-(U1-SDA3-Pad10)") (class "Default")
      (node (ref "U1") (pin "10") (pinfunction "SDA3_10") (pintype "bidirectional"))
    )
    (net (code "99") (name "unconnected-(U1-SDA4-Pad13)") (class "Default")
      (node (ref "U1") (pin "13") (pinfunction "SDA4_13") (pintype "bidirectional"))
    )
    (net (code "100") (name "unconnected-(U1-SDA5-Pad15)") (class "Default")
      (node (ref "U1") (pin "15") (pinfunction "SDA5_15") (pintype "bidirectional"))
    )
    (net (code "101") (name "unconnected-(U1-SDA6-Pad17)") (class "Default")
      (node (ref "U1") (pin "17") (pinfunction "SDA6_17") (pintype "bidirectional"))
    )
    (net (code "102") (name "unconnected-(U1-SDA7-Pad19)") (class "Default")
      (node (ref "U1") (pin "19") (pinfunction "SDA7_19") (pintype "bidirectional"))
    )
    (net (code "103") (name "unconnected-(X2A-S-Pad1)") (class "Default")
      (node (ref "X2") (pin "1") (pinfunction "S_1") (pintype "passive"))
    )
    (net (code "104") (name "unconnected-(X2C-S-Pad2)") (class "Default")
      (node (ref "X2") (pin "2") (pinfunction "S_2") (pintype "passive"))
    )
    (net (code "105") (name "unconnected-(X2F-S-Pad5)") (class "Default")
      (node (ref "X2") (pin "5") (pinfunction "S_5") (pintype "passive"))
    )
    (net (code "106") (name "unconnected-(X2H-S-Pad7)") (class "Default")
      (node (ref "X2") (pin "7") (pinfunction "S_7") (pintype "passive"))
    )
    (net (code "107") (name "unconnected-(X4A-S-Pad1)") (class "Default")
      (node (ref "X4") (pin "1") (pinfunction "S_1") (pintype "passive"))
    )
    (net (code "108") (name "unconnected-(X4C-S-Pad2)") (class "Default")
      (node (ref "X4") (pin "2") (pinfunction "S_2") (pintype "passive"))
    )
    (net (code "109") (name "unconnected-(X4F-S-Pad5)") (class "Default")
      (node (ref "X4") (pin "5") (pinfunction "S_5") (pintype "passive"))
    )
    (net (code "110") (name "unconnected-(X4H-S-Pad7)") (class "Default")
      (node (ref "X4") (pin "7") (pinfunction "S_7") (pintype "passive"))
    )
  )
)
